# PowerDD2.net
KiCad netlist of a schematic drawn in Altium Designer
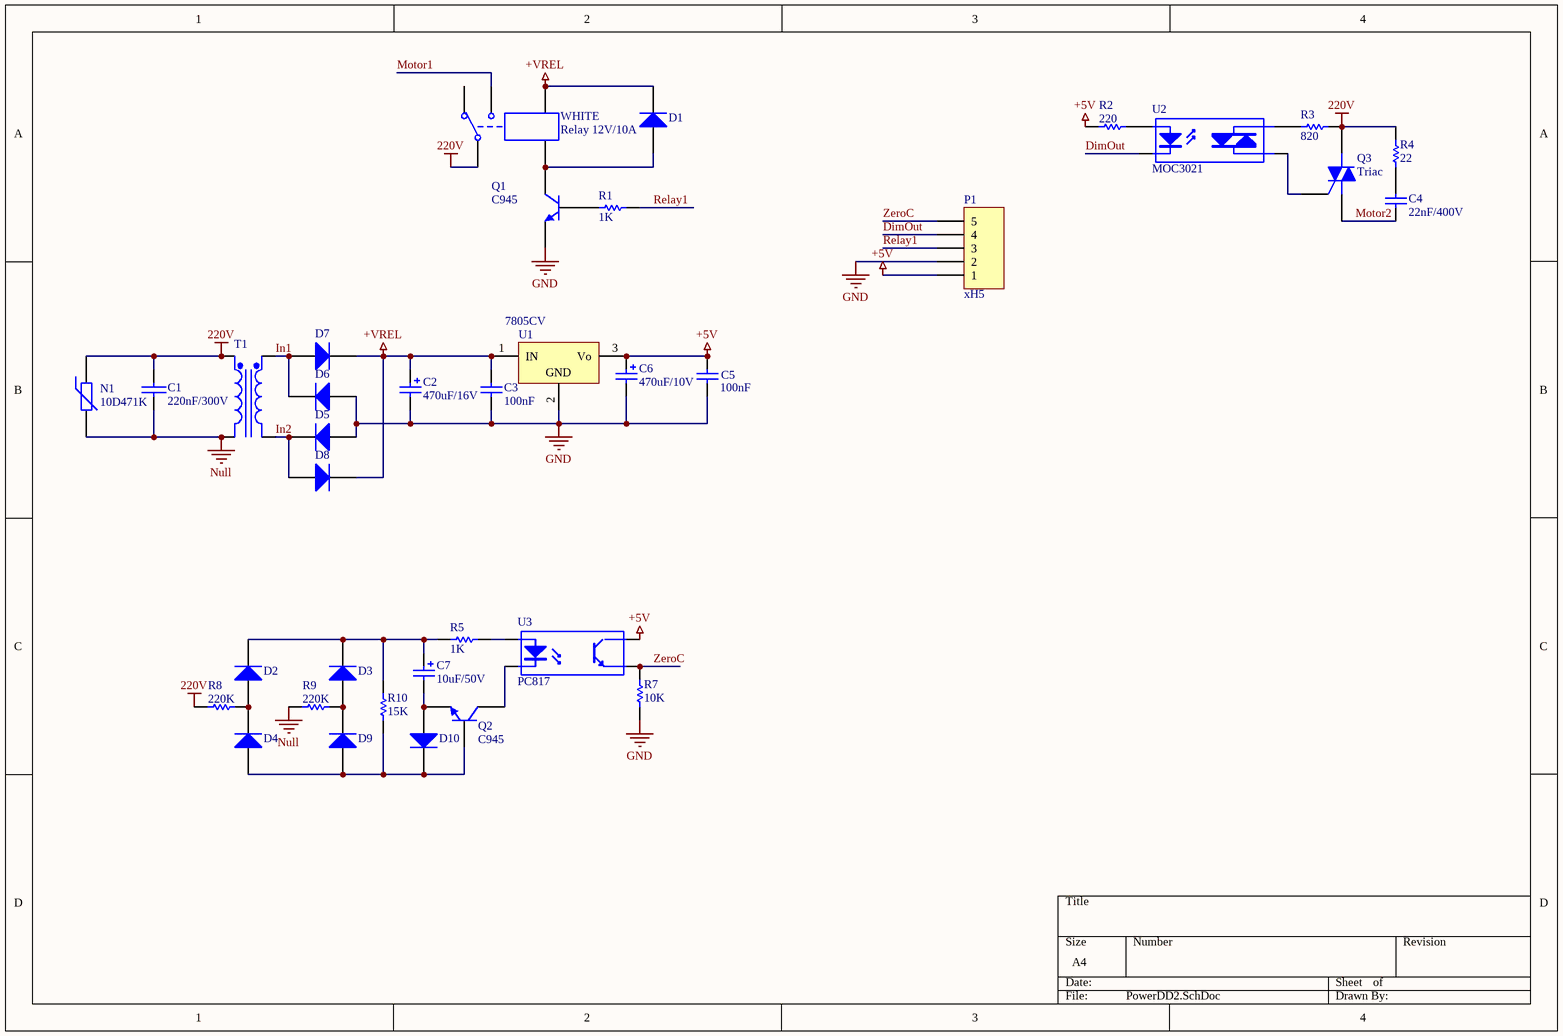
[diagram p0: PowerDD2.SchDoc]

(export (version "E")
  (design (tool "Eeschema 10.0.6"))
  (components
    (comp (ref "C1")
      (value "220nF/300V")
      (footprint "Cap15")
      (description "Line Cap")
      (libsource (lib "*") (part "CAP"))
    )
    (comp (ref "C2")
      (value "470uF/16V")
      (footprint "RB.2/.4")
      (description "Polarized Capacitor")
      (fields (field (name "PUBLISHER") "Altium Limited"))
      (libsource (lib "MySchLib") (part "Cap Pol"))
    )
    (comp (ref "C3")
      (value "100nF")
      (footprint "RAD0.2")
      (description "Capacitor np")
      (fields (field (name "PUBLISHER") "Altium Limited"))
      (libsource (lib "MySchLib") (part "Cap"))
    )
    (comp (ref "C4")
      (value "22nF/400V")
      (footprint "RAD0.2")
      (description "Capacitor")
      (fields (field (name "PUBLISHER") "Altium Limited"))
      (libsource (lib "MySchLib") (part "Cap"))
    )
    (comp (ref "C5")
      (value "100nF")
      (footprint "RAD0.2")
      (description "Capacitor np")
      (fields (field (name "PUBLISHER") "Altium Limited"))
      (libsource (lib "MySchLib") (part "Cap"))
    )
    (comp (ref "C6")
      (value "470uF/10V")
      (footprint "RB.2/.4")
      (description "Polarized Capacitor")
      (fields (field (name "PUBLISHER") "Altium Limited"))
      (libsource (lib "MySchLib") (part "Cap Pol"))
    )
    (comp (ref "C7")
      (value "10uF/50V")
      (footprint "RB.1/.2")
      (description "Polarized Capacitor")
      (fields (field (name "PUBLISHER") "Altium Limited"))
      (libsource (lib "MySchLib") (part "Cap Pol"))
    )
    (comp (ref "D1")
      (value "1N4148")
      (footprint "DIODE0.35")
      (description "1 Amp General Purpose Rectifier")
      (fields (field (name "PUBLISHER") "Altium Limited"))
      (libsource (lib "MySchLib") (part "Diode"))
    )
    (comp (ref "D2")
      (value "1N4007")
      (footprint "DIODE0.4")
      (fields (field (name "PUBLISHER") "Altium Limited"))
      (libsource (lib "MySchLib") (part "Diode"))
    )
    (comp (ref "D3")
      (value "1N4007")
      (footprint "DIODE0.4")
      (fields (field (name "PUBLISHER") "Altium Limited"))
      (libsource (lib "MySchLib") (part "Diode"))
    )
    (comp (ref "D4")
      (value "1N4007")
      (footprint "DIODE0.4")
      (fields (field (name "PUBLISHER") "Altium Limited"))
      (libsource (lib "MySchLib") (part "Diode"))
    )
    (comp (ref "D5")
      (value "1N4007")
      (footprint "DIODE0.4")
      (fields (field (name "PUBLISHER") "Altium Limited"))
      (libsource (lib "MySchLib") (part "Diode"))
    )
    (comp (ref "D6")
      (value "1N4007")
      (footprint "DIODE0.4")
      (fields (field (name "PUBLISHER") "Altium Limited"))
      (libsource (lib "MySchLib") (part "Diode"))
    )
    (comp (ref "D7")
      (value "1N4007")
      (footprint "DIODE0.4")
      (fields (field (name "PUBLISHER") "Altium Limited"))
      (libsource (lib "MySchLib") (part "Diode"))
    )
    (comp (ref "D8")
      (value "1N4007")
      (footprint "DIODE0.4")
      (fields (field (name "PUBLISHER") "Altium Limited"))
      (libsource (lib "MySchLib") (part "Diode"))
    )
    (comp (ref "D9")
      (value "1N4007")
      (footprint "DIODE0.4")
      (fields (field (name "PUBLISHER") "Altium Limited"))
      (libsource (lib "MySchLib") (part "Diode"))
    )
    (comp (ref "D10")
      (value "1N4007")
      (footprint "DIODE0.4")
      (fields (field (name "PUBLISHER") "Altium Limited"))
      (libsource (lib "MySchLib") (part "Diode"))
    )
    (comp (ref "N1")
      (value "10D471K")
      (footprint "varistor-10mil")
      (fields (field (name "PUBLISHER") "Altium Limited"))
      (libsource (lib "Miscellaneous Devices") (part "Res Varistor"))
    )
    (comp (ref "P1")
      (value "xH5")
      (footprint "CON5")
      (description "Header, 5-Pin")
      (fields (field (name "PUBLISHER") "Altium Limited"))
      (libsource (lib "Miscellaneous Connectors") (part "Header 5"))
    )
    (comp (ref "Q1")
      (value "C945")
      (footprint "TO92")
      (description "NPN General Purpose Amplifier")
      (fields (field (name "PUBLISHER") "Altium Limited"))
      (libsource (lib "MySchLib") (part "BC337"))
    )
    (comp (ref "Q2")
      (value "C945")
      (footprint "TO92")
      (description "NPN General Purpose Amplifier")
      (fields (field (name "PUBLISHER") "Altium Limited"))
      (libsource (lib "MySchLib") (part "BC337"))
    )
    (comp (ref "Q3")
      (value "Triac")
      (footprint "TO-220HS28")
      (description "Silicon Bidirectional Triode Thyristor")
      (fields (field (name "PUBLISHER") "Altium Limited"))
      (libsource (lib "Miscellaneous Devices") (part "Triac"))
    )
    (comp (ref "R1")
      (value "1K")
      (footprint "RES0.35")
      (description "Resistor")
      (fields (field (name "PUBLISHER") "Altium Limited"))
      (libsource (lib "MySchLib") (part "Resistor"))
    )
    (comp (ref "R2")
      (value "220")
      (footprint "RES0.35")
      (description "Resistor")
      (fields (field (name "PUBLISHER") "Altium Limited"))
      (libsource (lib "MySchLib") (part "Resistor"))
    )
    (comp (ref "R3")
      (value "820")
      (footprint "RES0.35")
      (description "Resistor")
      (fields (field (name "PUBLISHER") "Altium Limited"))
      (libsource (lib "MySchLib") (part "Resistor"))
    )
    (comp (ref "R4")
      (value "22")
      (footprint "RES0.35")
      (description "Resistor")
      (fields (field (name "PUBLISHER") "Altium Limited"))
      (libsource (lib "MySchLib") (part "Resistor"))
    )
    (comp (ref "R5")
      (value "1K")
      (footprint "RES0.35")
      (description "Resistor")
      (fields (field (name "PUBLISHER") "Altium Limited"))
      (libsource (lib "MySchLib") (part "Resistor"))
    )
    (comp (ref "R7")
      (value "10K")
      (footprint "RES0.35")
      (description "Resistor")
      (fields (field (name "PUBLISHER") "Altium Limited"))
      (libsource (lib "MySchLib") (part "Resistor"))
    )
    (comp (ref "R8")
      (value "220K")
      (footprint "RES0.35")
      (description "Resistor")
      (fields (field (name "PUBLISHER") "Altium Limited"))
      (libsource (lib "MySchLib") (part "Resistor"))
    )
    (comp (ref "R9")
      (value "220K")
      (footprint "RES0.35")
      (description "Resistor")
      (fields (field (name "PUBLISHER") "Altium Limited"))
      (libsource (lib "MySchLib") (part "Resistor"))
    )
    (comp (ref "R10")
      (value "15K")
      (footprint "RES0.35")
      (description "Resistor")
      (fields (field (name "PUBLISHER") "Altium Limited"))
      (libsource (lib "MySchLib") (part "Resistor"))
    )
    (comp (ref "T1")
      (value "Transformer")
      (footprint "Trans200mA")
      (description "6Volt-300mA")
      (fields (field (name "PUBLISHER") "Altium Limited"))
      (libsource (lib "MySchLib") (part "Transformer"))
    )
    (comp (ref "U1")
      (value "7805CV")
      (footprint "TO-220TriacHS")
      (description "Positive Voltage Regulator")
      (fields (field (name "PUBLISHER") "Altium Limited"))
      (libsource (lib "MySchLib") (part "7805"))
    )
    (comp (ref "U2")
      (value "MOC3021")
      (footprint "DIP6")
      (description "Opto-Triac")
      (fields (field (name "PUBLISHER") "Altium Limited"))
      (libsource (lib "MySchLib") (part "Opto TRIAC_1"))
    )
    (comp (ref "U3")
      (value "PC817")
      (footprint "DIP4-OPTO")
      (description "4-Pin Phototransistor Optocoupler")
      (fields (field (name "PUBLISHER") "Altium Limited"))
      (libsource (lib "MySchLib") (part "Optoisolator1"))
    )
    (comp (ref "WHITE")
      (value "Relay 12V/10A")
      (footprint "RELAY2")
      (description "Milon")
      (fields (field (name "PUBLISHER") "Altium Limited"))
      (libsource (lib "MySchLib") (part "Relay-SPDT"))
    )
  )
  (nets
    (net (code "1") (name "+5V") (class "Default")
      (node (ref "C5") (pin "2") (pinfunction "2_2") (pintype "passive"))
      (node (ref "C6") (pin "1") (pinfunction "1_1") (pintype "passive"))
      (node (ref "P1") (pin "1") (pinfunction "1_1") (pintype "passive"))
      (node (ref "R2") (pin "1") (pinfunction "1_1") (pintype "passive"))
      (node (ref "U1") (pin "3") (pinfunction "Vo_3") (pintype "power_in"))
      (node (ref "U3") (pin "4") (pinfunction "C_4") (pintype "passive"))
    )
    (net (code "2") (name "+VREL") (class "Default")
      (node (ref "C2") (pin "1") (pinfunction "1_1") (pintype "passive"))
      (node (ref "C3") (pin "2") (pinfunction "2_2") (pintype "passive"))
      (node (ref "D1") (pin "2") (pinfunction "K_2") (pintype "passive"))
      (node (ref "D7") (pin "2") (pinfunction "K_2") (pintype "passive"))
      (node (ref "D8") (pin "2") (pinfunction "K_2") (pintype "passive"))
      (node (ref "U1") (pin "1") (pinfunction "IN_1") (pintype "power_in"))
      (node (ref "WHITE") (pin "2") (pinfunction "C2_2") (pintype "passive"))
    )
    (net (code "3") (name "/DimOut") (class "Default")
      (node (ref "P1") (pin "4") (pinfunction "4_4") (pintype "passive"))
      (node (ref "U2") (pin "2") (pinfunction "K_2") (pintype "passive"))
    )
    (net (code "4") (name "/In1") (class "Default")
      (node (ref "D6") (pin "2") (pinfunction "K_2") (pintype "passive"))
      (node (ref "D7") (pin "1") (pinfunction "A_1") (pintype "passive"))
      (node (ref "T1") (pin "3") (pinfunction "Sec+_3") (pintype "passive"))
    )
    (net (code "5") (name "/In2") (class "Default")
      (node (ref "D5") (pin "2") (pinfunction "K_2") (pintype "passive"))
      (node (ref "D8") (pin "1") (pinfunction "A_1") (pintype "passive"))
      (node (ref "T1") (pin "4") (pinfunction "Sec-_4") (pintype "passive"))
    )
    (net (code "6") (name "/Motor1") (class "Default")
      (node (ref "WHITE") (pin "4") (pinfunction "NO_4") (pintype "passive"))
    )
    (net (code "7") (name "/Motor2") (class "Default")
      (node (ref "C4") (pin "1") (pinfunction "1_1") (pintype "passive"))
      (node (ref "Q3") (pin "1") (pinfunction "M1_1") (pintype "passive"))
    )
    (net (code "8") (name "/Relay1") (class "Default")
      (node (ref "P1") (pin "3") (pinfunction "3_3") (pintype "passive"))
      (node (ref "R1") (pin "1") (pinfunction "1_1") (pintype "passive"))
    )
    (net (code "9") (name "/ZeroC") (class "Default")
      (node (ref "P1") (pin "5") (pinfunction "5_5") (pintype "passive"))
      (node (ref "R7") (pin "1") (pinfunction "1_1") (pintype "passive"))
      (node (ref "U3") (pin "3") (pinfunction "E_3") (pintype "passive"))
    )
    (net (code "10") (name "220V") (class "Default")
      (node (ref "C1") (pin "1") (pinfunction "1_1") (pintype "passive"))
      (node (ref "N1") (pin "1") (pinfunction "1_1") (pintype "passive"))
      (node (ref "Q3") (pin "2") (pinfunction "M2_2") (pintype "passive"))
      (node (ref "R3") (pin "1") (pinfunction "1_1") (pintype "passive"))
      (node (ref "R4") (pin "1") (pinfunction "1_1") (pintype "passive"))
      (node (ref "R8") (pin "1") (pinfunction "1_1") (pintype "passive"))
      (node (ref "T1") (pin "1") (pinfunction "Pri+_1") (pintype "passive"))
      (node (ref "WHITE") (pin "3") (pinfunction "Com_3") (pintype "passive"))
    )
    (net (code "11") (name "GND") (class "Default")
      (node (ref "C2") (pin "2") (pinfunction "2_2") (pintype "passive"))
      (node (ref "C3") (pin "1") (pinfunction "1_1") (pintype "passive"))
      (node (ref "C5") (pin "1") (pinfunction "1_1") (pintype "passive"))
      (node (ref "C6") (pin "2") (pinfunction "2_2") (pintype "passive"))
      (node (ref "D5") (pin "1") (pinfunction "A_1") (pintype "passive"))
      (node (ref "D6") (pin "1") (pinfunction "A_1") (pintype "passive"))
      (node (ref "P1") (pin "2") (pinfunction "2_2") (pintype "passive"))
      (node (ref "Q1") (pin "3") (pinfunction "E_3") (pintype "passive"))
      (node (ref "R7") (pin "2") (pinfunction "2_2") (pintype "passive"))
      (node (ref "U1") (pin "2") (pinfunction "OUT_2") (pintype "power_in"))
    )
    (net (code "12") (name "Net-(C4-Pad2)") (class "Default")
      (node (ref "C4") (pin "2") (pinfunction "2_2") (pintype "passive"))
      (node (ref "R4") (pin "2") (pinfunction "2_2") (pintype "passive"))
    )
    (net (code "13") (name "Net-(D1-A)") (class "Default")
      (node (ref "D1") (pin "1") (pinfunction "A_1") (pintype "passive"))
      (node (ref "Q1") (pin "2") (pinfunction "C_2") (pintype "passive"))
      (node (ref "WHITE") (pin "1") (pinfunction "C1_1") (pintype "passive"))
    )
    (net (code "14") (name "Net-(D2-A)") (class "Default")
      (node (ref "D2") (pin "1") (pinfunction "A_1") (pintype "passive"))
      (node (ref "D4") (pin "2") (pinfunction "K_2") (pintype "passive"))
      (node (ref "R8") (pin "2") (pinfunction "2_2") (pintype "passive"))
    )
    (net (code "15") (name "Net-(D2-K)") (class "Default")
      (node (ref "C7") (pin "1") (pinfunction "1_1") (pintype "passive"))
      (node (ref "D2") (pin "2") (pinfunction "K_2") (pintype "passive"))
      (node (ref "D3") (pin "2") (pinfunction "K_2") (pintype "passive"))
      (node (ref "R10") (pin "2") (pinfunction "2_2") (pintype "passive"))
      (node (ref "R5") (pin "2") (pinfunction "2_2") (pintype "passive"))
    )
    (net (code "16") (name "Net-(D3-A)") (class "Default")
      (node (ref "D3") (pin "1") (pinfunction "A_1") (pintype "passive"))
      (node (ref "D9") (pin "2") (pinfunction "K_2") (pintype "passive"))
      (node (ref "R9") (pin "2") (pinfunction "2_2") (pintype "passive"))
    )
    (net (code "17") (name "Net-(D10-A)") (class "Default")
      (node (ref "C7") (pin "2") (pinfunction "2_2") (pintype "passive"))
      (node (ref "D10") (pin "1") (pinfunction "A_1") (pintype "passive"))
      (node (ref "Q2") (pin "3") (pinfunction "E_3") (pintype "passive"))
    )
    (net (code "18") (name "Net-(D10-K)") (class "Default")
      (node (ref "D10") (pin "2") (pinfunction "K_2") (pintype "passive"))
      (node (ref "D4") (pin "1") (pinfunction "A_1") (pintype "passive"))
      (node (ref "D9") (pin "1") (pinfunction "A_1") (pintype "passive"))
      (node (ref "Q2") (pin "1") (pinfunction "B_1") (pintype "passive"))
      (node (ref "R10") (pin "1") (pinfunction "1_1") (pintype "passive"))
    )
    (net (code "19") (name "Net-(Q1-B)") (class "Default")
      (node (ref "Q1") (pin "1") (pinfunction "B_1") (pintype "passive"))
      (node (ref "R1") (pin "2") (pinfunction "2_2") (pintype "passive"))
    )
    (net (code "20") (name "Net-(Q2-C)") (class "Default")
      (node (ref "Q2") (pin "2") (pinfunction "C_2") (pintype "passive"))
      (node (ref "U3") (pin "2") (pinfunction "K_2") (pintype "passive"))
    )
    (net (code "21") (name "Net-(Q3-G)") (class "Default")
      (node (ref "Q3") (pin "3") (pinfunction "G_3") (pintype "passive"))
      (node (ref "U2") (pin "4") (pinfunction "A/K_4") (pintype "passive"))
    )
    (net (code "22") (name "Net-(R3-Pad2)") (class "Default")
      (node (ref "R3") (pin "2") (pinfunction "2_2") (pintype "passive"))
      (node (ref "U2") (pin "6") (pinfunction "A/K_6") (pintype "passive"))
    )
    (net (code "23") (name "Net-(U2-A)") (class "Default")
      (node (ref "R2") (pin "2") (pinfunction "2_2") (pintype "passive"))
      (node (ref "U2") (pin "1") (pinfunction "A_1") (pintype "passive"))
    )
    (net (code "24") (name "Net-(U3-A)") (class "Default")
      (node (ref "R5") (pin "1") (pinfunction "1_1") (pintype "passive"))
      (node (ref "U3") (pin "1") (pinfunction "A_1") (pintype "passive"))
    )
    (net (code "25") (name "Null") (class "Default")
      (node (ref "C1") (pin "2") (pinfunction "2_2") (pintype "passive"))
      (node (ref "N1") (pin "2") (pinfunction "2_2") (pintype "passive"))
      (node (ref "R9") (pin "1") (pinfunction "1_1") (pintype "passive"))
      (node (ref "T1") (pin "2") (pinfunction "Pri-_2") (pintype "passive"))
    )
    (net (code "26") (name "unconnected-(WHITE-NC-Pad5)") (class "Default")
      (node (ref "WHITE") (pin "5") (pinfunction "NC_5") (pintype "passive"))
    )
  )
)
